# 2017_CARTE_4_MOFSET.net
KiCad netlist of a schematic drawn in Altium Designer
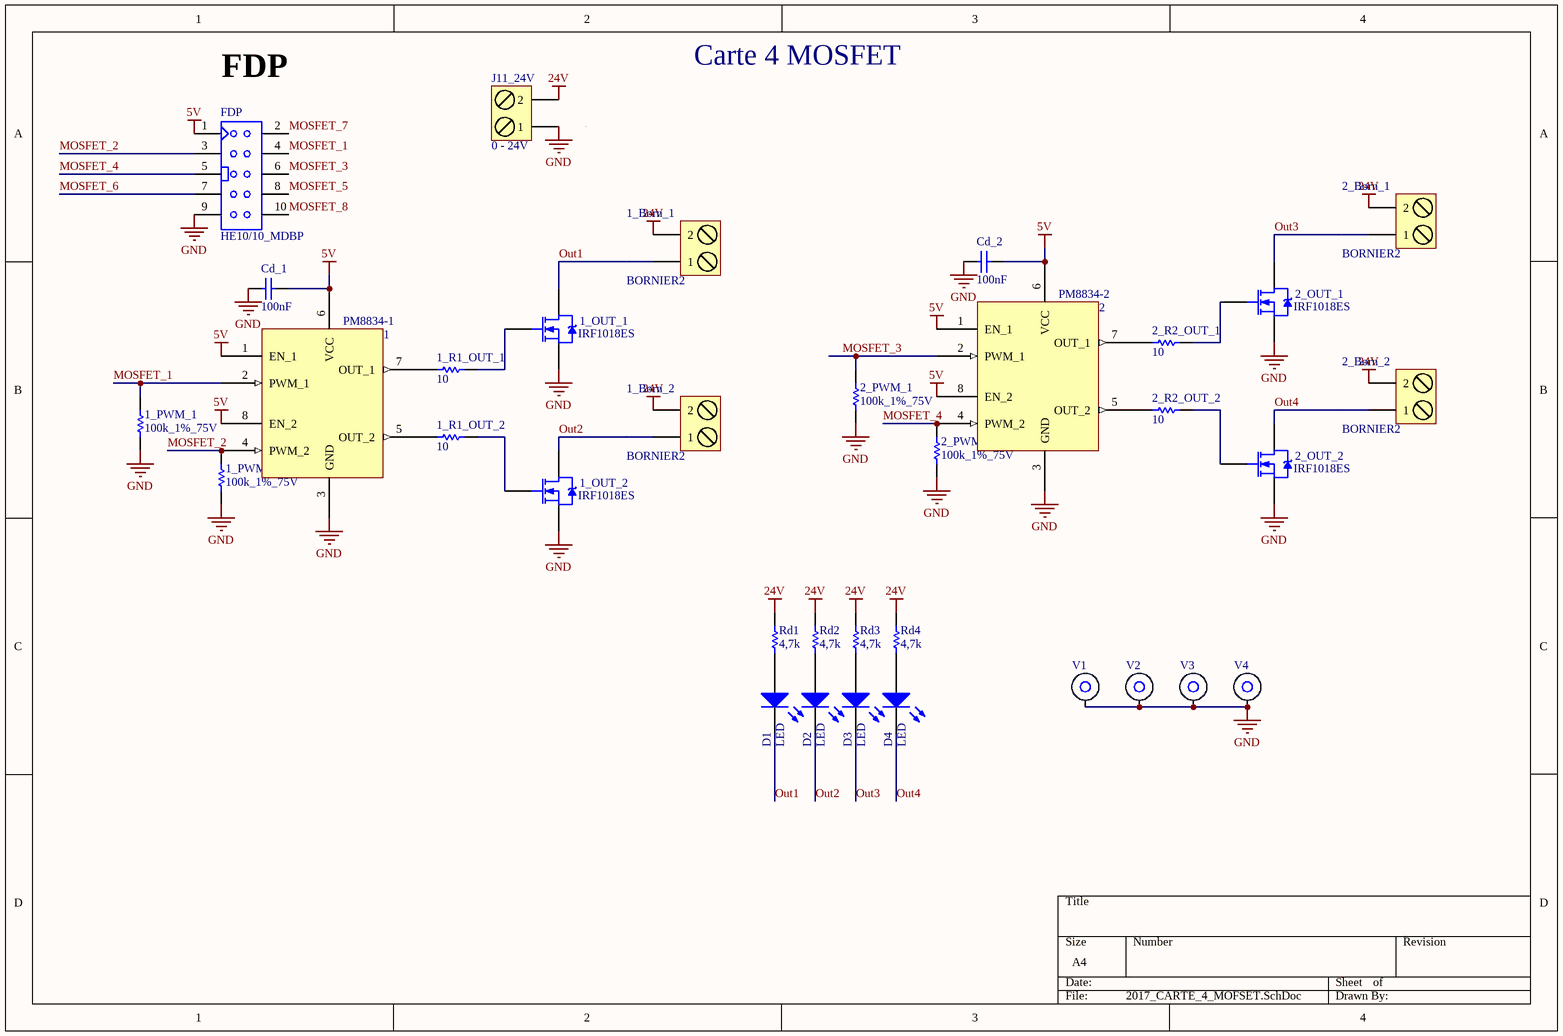
[diagram p0: 2017_CARTE_4_MOFSET.SchDoc]

(export (version "E")
  (design (tool "Eeschema 10.0.6"))
  (components
    (comp (ref "1")
      (value "PM8834-1")
      (footprint "SO8_N")
      (description "4 A dual low-side MOSFET driver")
      (libsource (lib "_ROBOT") (part "PM8834"))
    )
    (comp (ref "1_Born_1")
      (value "BORNIER2")
      (footprint "BORNIER2")
      (description "Terminal blocks, 2 pins, pitch=5mm")
      (libsource (lib "Connecteur") (part "BORNIER2"))
    )
    (comp (ref "1_Born_2")
      (value "BORNIER2")
      (footprint "BORNIER2")
      (description "Terminal blocks, 2 pins, pitch=5mm")
      (libsource (lib "Connecteur") (part "BORNIER2"))
    )
    (comp (ref "1_OUT_1")
      (value "IRF1018ES")
      (footprint "_ROBOT:D2PAK_GROS_PAD")
      (description "HEXFET N-Channel Power MOSFET")
      (fields (field (name "PUBLISHER") "Altium Limited"))
      (libsource (lib "IR Discrete MOSFET - Power") (part "IRF1010S"))
    )
    (comp (ref "1_OUT_2")
      (value "IRF1018ES")
      (footprint "D2PAK_GROS_PAD")
      (description "HEXFET N-Channel Power MOSFET")
      (fields (field (name "PUBLISHER") "Altium Limited"))
      (libsource (lib "IR Discrete MOSFET - Power") (part "IRF1010S"))
    )
    (comp (ref "1_PWM_1")
      (value "100k_1%_75V")
      (footprint "R1206_N")
      (description "Resistor")
      (fields (field (name "PUBLISHER") "Altium Limited"))
      (libsource (lib "DG_Resistance") (part "Resistor"))
    )
    (comp (ref "1_PWM_2")
      (value "100k_1%_75V")
      (footprint "R1206_N")
      (description "Resistor")
      (fields (field (name "PUBLISHER") "Altium Limited"))
      (libsource (lib "DG_Resistance") (part "Resistor"))
    )
    (comp (ref "1_R1_OUT_1")
      (value "10")
      (footprint "R1206_N")
      (description "Resistor")
      (fields (field (name "PUBLISHER") "Altium Limited"))
      (libsource (lib "_ROBOT") (part "Resistor"))
    )
    (comp (ref "1_R1_OUT_2")
      (value "10")
      (footprint "R1206_N")
      (description "Resistor")
      (fields (field (name "PUBLISHER") "Altium Limited"))
      (libsource (lib "_ROBOT") (part "Resistor"))
    )
    (comp (ref "2")
      (value "PM8834-2")
      (footprint "SO8_N")
      (description "4 A dual low-side MOSFET driver")
      (libsource (lib "_ROBOT") (part "PM8834"))
    )
    (comp (ref "2_Born_1")
      (value "BORNIER2")
      (footprint "BORNIER2")
      (description "Terminal blocks, 2 pins, pitch=5mm")
      (libsource (lib "Connecteur") (part "BORNIER2"))
    )
    (comp (ref "2_Born_2")
      (value "BORNIER2")
      (footprint "BORNIER2")
      (description "Terminal blocks, 2 pins, pitch=5mm")
      (libsource (lib "Connecteur") (part "BORNIER2"))
    )
    (comp (ref "2_OUT_1")
      (value "IRF1018ES")
      (footprint "D2PAK_GROS_PAD")
      (description "HEXFET N-Channel Power MOSFET")
      (fields (field (name "PUBLISHER") "Altium Limited"))
      (libsource (lib "IR Discrete MOSFET - Power") (part "IRF1010S"))
    )
    (comp (ref "2_OUT_2")
      (value "IRF1018ES")
      (footprint "D2PAK_GROS_PAD")
      (description "HEXFET N-Channel Power MOSFET")
      (fields (field (name "PUBLISHER") "Altium Limited"))
      (libsource (lib "IR Discrete MOSFET - Power") (part "IRF1010S"))
    )
    (comp (ref "2_PWM_1")
      (value "100k_1%_75V")
      (footprint "R1206_N")
      (description "Resistor")
      (fields (field (name "PUBLISHER") "Altium Limited"))
      (libsource (lib "DG_Resistance") (part "Resistor"))
    )
    (comp (ref "2_PWM_2")
      (value "100k_1%_75V")
      (footprint "R1206_N")
      (description "Resistor")
      (fields (field (name "PUBLISHER") "Altium Limited"))
      (libsource (lib "DG_Resistance") (part "Resistor"))
    )
    (comp (ref "2_R2_OUT_1")
      (value "10")
      (footprint "R1206_N")
      (description "Resistor")
      (fields (field (name "PUBLISHER") "Altium Limited"))
      (libsource (lib "_ROBOT") (part "Resistor"))
    )
    (comp (ref "2_R2_OUT_2")
      (value "10")
      (footprint "R1206_N")
      (description "Resistor")
      (fields (field (name "PUBLISHER") "Altium Limited"))
      (libsource (lib "_ROBOT") (part "Resistor"))
    )
    (comp (ref "Cd_1")
      (value "100nF")
      (footprint "C0805_N")
      (description "Capacitor")
      (fields (field (name "PUBLISHER") "Altium Limited"))
      (libsource (lib "_ROBOT") (part "Condensateur"))
    )
    (comp (ref "Cd_2")
      (value "100nF")
      (footprint "C0805_N")
      (description "Capacitor")
      (fields (field (name "PUBLISHER") "Altium Limited"))
      (libsource (lib "_ROBOT") (part "Condensateur"))
    )
    (comp (ref "D1")
      (value "LED")
      (footprint "LED_0805")
      (description "Typical LED")
      (fields (field (name "PUBLISHER") "Altium Limited"))
      (libsource (lib "_ROBOT") (part "LED"))
    )
    (comp (ref "D2")
      (value "LED")
      (footprint "LED_0805")
      (description "Typical LED")
      (fields (field (name "PUBLISHER") "Altium Limited"))
      (libsource (lib "_ROBOT") (part "LED"))
    )
    (comp (ref "D3")
      (value "LED")
      (footprint "LED_0805")
      (description "Typical LED")
      (fields (field (name "PUBLISHER") "Altium Limited"))
      (libsource (lib "_ROBOT") (part "LED"))
    )
    (comp (ref "D4")
      (value "LED")
      (footprint "LED_0805")
      (description "Typical LED")
      (fields (field (name "PUBLISHER") "Altium Limited"))
      (libsource (lib "_ROBOT") (part "LED"))
    )
    (comp (ref "FDP")
      (value "HE10/10_MALE_DROIT_BAS_PROFIL")
      (footprint "HE10/10_M_D_BP")
      (description "EMBASE HE10/10 MALE DROIT BAS PROFIL")
      (fields (field (name "TYPE") "HE10/10_MDBP"))
      (libsource (lib "connecteurs") (part "HE10/10_MALE_DROIT_BAS_PROFIL"))
    )
    (comp (ref "J11_24V")
      (value "0 - 24V")
      (footprint "BORNIER2_FEM_COUDE")
      (description "Terminal blocks, 2 pins, pitch=5mm")
      (libsource (lib "miniprojet") (part "BORNIER2"))
    )
    (comp (ref "Rd1")
      (value "4,7k")
      (footprint "R1206_N")
      (description "Resistor")
      (fields (field (name "PUBLISHER") "Altium Limited"))
      (libsource (lib "_ROBOT") (part "Resistor"))
    )
    (comp (ref "Rd2")
      (value "4,7k")
      (footprint "R1206_N")
      (description "Resistor")
      (fields (field (name "PUBLISHER") "Altium Limited"))
      (libsource (lib "_ROBOT") (part "Resistor"))
    )
    (comp (ref "Rd3")
      (value "4,7k")
      (footprint "R1206_N")
      (description "Resistor")
      (fields (field (name "PUBLISHER") "Altium Limited"))
      (libsource (lib "_ROBOT") (part "Resistor"))
    )
    (comp (ref "Rd4")
      (value "4,7k")
      (footprint "R1206_N")
      (description "Resistor")
      (fields (field (name "PUBLISHER") "Altium Limited"))
      (libsource (lib "_ROBOT") (part "Resistor"))
    )
    (comp (ref "V1")
      (value "Entretoise WURTH CMS")
      (footprint "ENTRETOISE_CMS")
      (description "Entretoise Wurth")
      (fields (field (name "PUBLISHER") "Damien Guitton"))
      (libsource (lib "_ROBOT") (part "Entretoise WURTH CMS"))
    )
    (comp (ref "V2")
      (value "Entretoise WURTH CMS")
      (footprint "ENTRETOISE_CMS")
      (description "Entretoise Wurth")
      (fields (field (name "PUBLISHER") "Damien Guitton"))
      (libsource (lib "_ROBOT") (part "Entretoise WURTH CMS"))
    )
    (comp (ref "V3")
      (value "Entretoise WURTH CMS")
      (footprint "ENTRETOISE_CMS")
      (description "Entretoise Wurth")
      (fields (field (name "PUBLISHER") "Damien Guitton"))
      (libsource (lib "_ROBOT") (part "Entretoise WURTH CMS"))
    )
    (comp (ref "V4")
      (value "Entretoise WURTH CMS")
      (footprint "ENTRETOISE_CMS")
      (description "Entretoise Wurth")
      (fields (field (name "PUBLISHER") "Damien Guitton"))
      (libsource (lib "_ROBOT") (part "Entretoise WURTH CMS"))
    )
  )
  (nets
    (net (code "1") (name "/MOSFET_1") (class "Default")
      (node (ref "1") (pin "2") (pinfunction "PWM_1_2") (pintype "input"))
      (node (ref "1_PWM_1") (pin "2") (pinfunction "2_2") (pintype "passive"))
      (node (ref "FDP") (pin "4") (pinfunction "4_4") (pintype "passive"))
    )
    (net (code "2") (name "/MOSFET_2") (class "Default")
      (node (ref "1") (pin "4") (pinfunction "PWM_2_4") (pintype "input"))
      (node (ref "1_PWM_2") (pin "2") (pinfunction "2_2") (pintype "passive"))
      (node (ref "FDP") (pin "3") (pinfunction "3_3") (pintype "passive"))
    )
    (net (code "3") (name "/MOSFET_3") (class "Default")
      (node (ref "2") (pin "2") (pinfunction "PWM_1_2") (pintype "input"))
      (node (ref "2_PWM_1") (pin "2") (pinfunction "2_2") (pintype "passive"))
      (node (ref "FDP") (pin "6") (pinfunction "6_6") (pintype "passive"))
    )
    (net (code "4") (name "/MOSFET_4") (class "Default")
      (node (ref "2") (pin "4") (pinfunction "PWM_2_4") (pintype "input"))
      (node (ref "2_PWM_2") (pin "2") (pinfunction "2_2") (pintype "passive"))
      (node (ref "FDP") (pin "5") (pinfunction "5_5") (pintype "passive"))
    )
    (net (code "5") (name "/MOSFET_5") (class "Default")
      (node (ref "FDP") (pin "8") (pinfunction "8_8") (pintype "passive"))
    )
    (net (code "6") (name "/MOSFET_6") (class "Default")
      (node (ref "FDP") (pin "7") (pinfunction "7_7") (pintype "passive"))
    )
    (net (code "7") (name "/MOSFET_7") (class "Default")
      (node (ref "FDP") (pin "2") (pinfunction "2_2") (pintype "passive"))
    )
    (net (code "8") (name "/MOSFET_8") (class "Default")
      (node (ref "FDP") (pin "10") (pinfunction "10_10") (pintype "passive"))
    )
    (net (code "9") (name "/Out1") (class "Default")
      (node (ref "1_Born_1") (pin "1") (pinfunction "1_1") (pintype "passive"))
      (node (ref "1_OUT_1") (pin "2") (pinfunction "D_2") (pintype "passive"))
      (node (ref "D1") (pin "2") (pinfunction "K_2") (pintype "passive"))
    )
    (net (code "10") (name "/Out2") (class "Default")
      (node (ref "1_Born_2") (pin "1") (pinfunction "1_1") (pintype "passive"))
      (node (ref "1_OUT_2") (pin "2") (pinfunction "D_2") (pintype "passive"))
      (node (ref "D2") (pin "2") (pinfunction "K_2") (pintype "passive"))
    )
    (net (code "11") (name "/Out3") (class "Default")
      (node (ref "2_Born_1") (pin "1") (pinfunction "1_1") (pintype "passive"))
      (node (ref "2_OUT_1") (pin "2") (pinfunction "D_2") (pintype "passive"))
      (node (ref "D3") (pin "2") (pinfunction "K_2") (pintype "passive"))
    )
    (net (code "12") (name "/Out4") (class "Default")
      (node (ref "2_Born_2") (pin "1") (pinfunction "1_1") (pintype "passive"))
      (node (ref "2_OUT_2") (pin "2") (pinfunction "D_2") (pintype "passive"))
      (node (ref "D4") (pin "2") (pinfunction "K_2") (pintype "passive"))
    )
    (net (code "13") (name "5V") (class "Default")
      (node (ref "1") (pin "1") (pinfunction "EN_1_1") (pintype "passive"))
      (node (ref "1") (pin "6") (pinfunction "VCC_6") (pintype "power_in"))
      (node (ref "1") (pin "8") (pinfunction "EN_2_8") (pintype "passive"))
      (node (ref "2") (pin "1") (pinfunction "EN_1_1") (pintype "passive"))
      (node (ref "2") (pin "6") (pinfunction "VCC_6") (pintype "power_in"))
      (node (ref "2") (pin "8") (pinfunction "EN_2_8") (pintype "passive"))
      (node (ref "Cd_1") (pin "2") (pinfunction "2_2") (pintype "passive"))
      (node (ref "Cd_2") (pin "2") (pinfunction "2_2") (pintype "passive"))
      (node (ref "FDP") (pin "1") (pinfunction "1_1") (pintype "passive"))
    )
    (net (code "14") (name "24V") (class "Default")
      (node (ref "1_Born_1") (pin "2") (pinfunction "2_2") (pintype "passive"))
      (node (ref "1_Born_2") (pin "2") (pinfunction "2_2") (pintype "passive"))
      (node (ref "2_Born_1") (pin "2") (pinfunction "2_2") (pintype "passive"))
      (node (ref "2_Born_2") (pin "2") (pinfunction "2_2") (pintype "passive"))
      (node (ref "J11_24V") (pin "2") (pinfunction "2_2") (pintype "passive"))
      (node (ref "Rd1") (pin "1") (pinfunction "1_1") (pintype "passive"))
      (node (ref "Rd2") (pin "1") (pinfunction "1_1") (pintype "passive"))
      (node (ref "Rd3") (pin "1") (pinfunction "1_1") (pintype "passive"))
      (node (ref "Rd4") (pin "1") (pinfunction "1_1") (pintype "passive"))
    )
    (net (code "15") (name "GND") (class "Default")
      (node (ref "1") (pin "3") (pinfunction "GND_3") (pintype "power_in"))
      (node (ref "1_OUT_1") (pin "3") (pinfunction "S_3") (pintype "passive"))
      (node (ref "1_OUT_2") (pin "3") (pinfunction "S_3") (pintype "passive"))
      (node (ref "1_PWM_1") (pin "1") (pinfunction "1_1") (pintype "passive"))
      (node (ref "1_PWM_2") (pin "1") (pinfunction "1_1") (pintype "passive"))
      (node (ref "2") (pin "3") (pinfunction "GND_3") (pintype "power_in"))
      (node (ref "2_OUT_1") (pin "3") (pinfunction "S_3") (pintype "passive"))
      (node (ref "2_OUT_2") (pin "3") (pinfunction "S_3") (pintype "passive"))
      (node (ref "2_PWM_1") (pin "1") (pinfunction "1_1") (pintype "passive"))
      (node (ref "2_PWM_2") (pin "1") (pinfunction "1_1") (pintype "passive"))
      (node (ref "Cd_1") (pin "1") (pinfunction "1_1") (pintype "passive"))
      (node (ref "Cd_2") (pin "1") (pinfunction "1_1") (pintype "passive"))
      (node (ref "FDP") (pin "9") (pinfunction "9_9") (pintype "passive"))
      (node (ref "J11_24V") (pin "1") (pinfunction "1_1") (pintype "passive"))
      (node (ref "V1") (pin "1") (pinfunction "1_1") (pintype "passive"))
      (node (ref "V2") (pin "1") (pinfunction "1_1") (pintype "passive"))
      (node (ref "V3") (pin "1") (pinfunction "1_1") (pintype "passive"))
      (node (ref "V4") (pin "1") (pinfunction "1_1") (pintype "passive"))
    )
    (net (code "16") (name "Net-(1-OUT_1)") (class "Default")
      (node (ref "1") (pin "7") (pinfunction "OUT_1_7") (pintype "output"))
      (node (ref "1_R1_OUT_1") (pin "1") (pinfunction "1_1") (pintype "passive"))
    )
    (net (code "17") (name "Net-(1-OUT_2)") (class "Default")
      (node (ref "1") (pin "5") (pinfunction "OUT_2_5") (pintype "output"))
      (node (ref "1_R1_OUT_2") (pin "1") (pinfunction "1_1") (pintype "passive"))
    )
    (net (code "18") (name "Net-(1_OUT_1-G)") (class "Default")
      (node (ref "1_OUT_1") (pin "1") (pinfunction "G_1") (pintype "passive"))
      (node (ref "1_R1_OUT_1") (pin "2") (pinfunction "2_2") (pintype "passive"))
    )
    (net (code "19") (name "Net-(1_OUT_2-G)") (class "Default")
      (node (ref "1_OUT_2") (pin "1") (pinfunction "G_1") (pintype "passive"))
      (node (ref "1_R1_OUT_2") (pin "2") (pinfunction "2_2") (pintype "passive"))
    )
    (net (code "20") (name "Net-(2-OUT_1)") (class "Default")
      (node (ref "2") (pin "7") (pinfunction "OUT_1_7") (pintype "output"))
      (node (ref "2_R2_OUT_1") (pin "1") (pinfunction "1_1") (pintype "passive"))
    )
    (net (code "21") (name "Net-(2-OUT_2)") (class "Default")
      (node (ref "2") (pin "5") (pinfunction "OUT_2_5") (pintype "output"))
      (node (ref "2_R2_OUT_2") (pin "1") (pinfunction "1_1") (pintype "passive"))
    )
    (net (code "22") (name "Net-(2_OUT_1-G)") (class "Default")
      (node (ref "2_OUT_1") (pin "1") (pinfunction "G_1") (pintype "passive"))
      (node (ref "2_R2_OUT_1") (pin "2") (pinfunction "2_2") (pintype "passive"))
    )
    (net (code "23") (name "Net-(2_OUT_2-G)") (class "Default")
      (node (ref "2_OUT_2") (pin "1") (pinfunction "G_1") (pintype "passive"))
      (node (ref "2_R2_OUT_2") (pin "2") (pinfunction "2_2") (pintype "passive"))
    )
    (net (code "24") (name "Net-(D1-A)") (class "Default")
      (node (ref "D1") (pin "1") (pinfunction "A_1") (pintype "passive"))
      (node (ref "Rd1") (pin "2") (pinfunction "2_2") (pintype "passive"))
    )
    (net (code "25") (name "Net-(D2-A)") (class "Default")
      (node (ref "D2") (pin "1") (pinfunction "A_1") (pintype "passive"))
      (node (ref "Rd2") (pin "2") (pinfunction "2_2") (pintype "passive"))
    )
    (net (code "26") (name "Net-(D3-A)") (class "Default")
      (node (ref "D3") (pin "1") (pinfunction "A_1") (pintype "passive"))
      (node (ref "Rd3") (pin "2") (pinfunction "2_2") (pintype "passive"))
    )
    (net (code "27") (name "Net-(D4-A)") (class "Default")
      (node (ref "D4") (pin "1") (pinfunction "A_1") (pintype "passive"))
      (node (ref "Rd4") (pin "2") (pinfunction "2_2") (pintype "passive"))
    )
  )
)
